# IO.net
KiCad netlist of a schematic drawn in Altium Designer
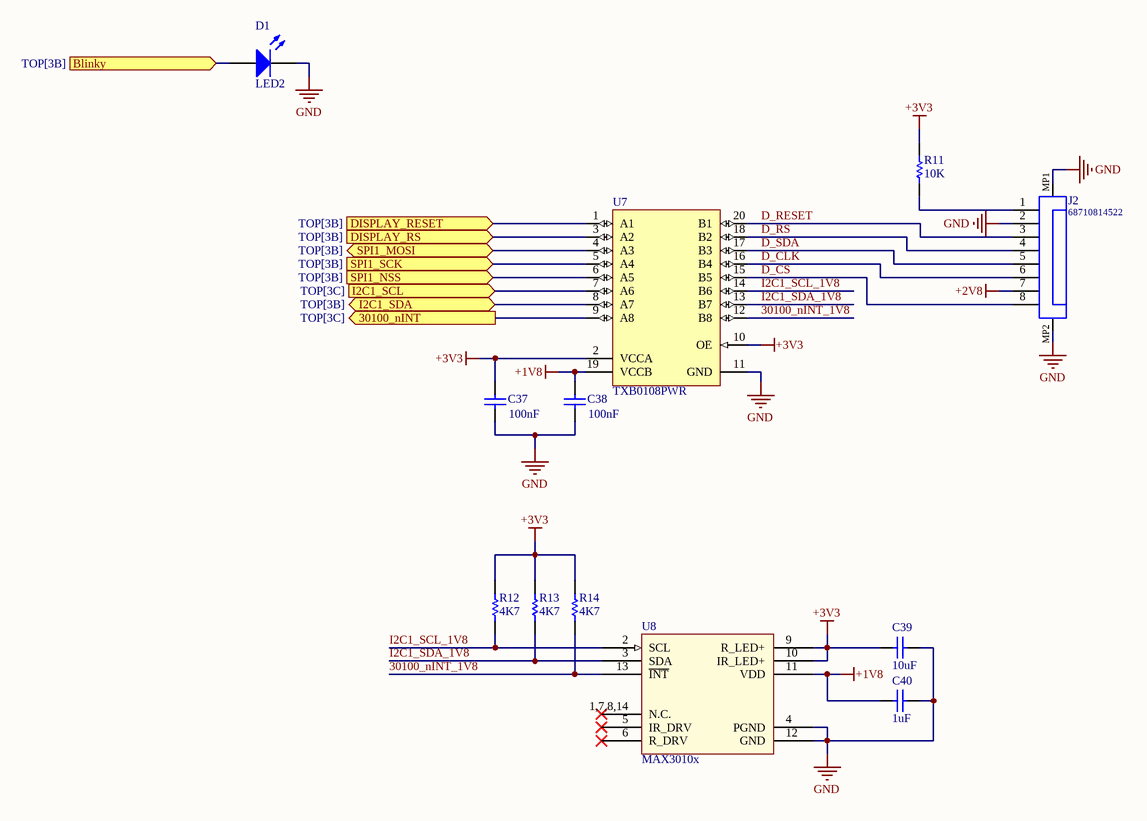
[diagram p0: IO.SchDoc]

(export (version "E")
  (design (tool "Eeschema 10.0.6"))
  (components
    (comp (ref "C37")
      (value "100nF")
      (footprint "C_0603")
      (description "Capacitor")
      (fields (field (name "Comment") "Cap") (field (name "PUBLISHER") "Altium Limited"))
      (libsource (lib "Miscellaneous Devices") (part "Cap"))
    )
    (comp (ref "C38")
      (value "100nF")
      (footprint "C_0603")
      (description "Capacitor")
      (fields (field (name "Comment") "Cap") (field (name "PUBLISHER") "Altium Limited"))
      (libsource (lib "Miscellaneous Devices") (part "Cap"))
    )
    (comp (ref "C39")
      (value "10uF")
      (footprint "C_0603")
      (description "Capacitor")
      (fields (field (name "Comment") "Cap") (field (name "PUBLISHER") "Altium Limited"))
      (libsource (lib "Miscellaneous Devices") (part "Cap"))
    )
    (comp (ref "C40")
      (value "1uF")
      (footprint "C_0603")
      (description "Capacitor")
      (fields (field (name "Comment") "Cap") (field (name "PUBLISHER") "Altium Limited"))
      (libsource (lib "Miscellaneous Devices") (part "Cap"))
    )
    (comp (ref "D1")
      (value "LED2")
      (footprint "D-0603")
      (description "Typical RED, GREEN, YELLOW, AMBER GaAs LED")
      (fields (field (name "PUBLISHER") "Altium Limited"))
      (libsource (lib "Miscellaneous Devices") (part "LED2"))
    )
    (comp (ref "J2")
      (value "68710814522")
      (footprint "68710814522")
      (description "SMT ZIF Connectors WR-FPC, Horizontal, Bottom Contact, pitch 0.5 mm, 8 pins")
      (fields (field (name "MANUFACTURER") "Wurth Elektronik") (field (name "PUBLISHER") "WurthElektronik"))
      (libsource (lib "Altium Content Vault") (part "WE-68X1081XXX22-8"))
    )
    (comp (ref "R11")
      (value "10K")
      (footprint "C_0603")
      (description "Resistor")
      (fields (field (name "Comment") "Res1") (field (name "PUBLISHER") "Altium Limited"))
      (libsource (lib "Miscellaneous Devices") (part "Res1"))
    )
    (comp (ref "R12")
      (value "4K7")
      (footprint "C_0603")
      (description "Resistor")
      (fields (field (name "Comment") "Res1") (field (name "PUBLISHER") "Altium Limited"))
      (libsource (lib "Miscellaneous Devices") (part "Res1"))
    )
    (comp (ref "R13")
      (value "4K7")
      (footprint "C_0603")
      (description "Resistor")
      (fields (field (name "Comment") "Res1") (field (name "PUBLISHER") "Altium Limited"))
      (libsource (lib "Miscellaneous Devices") (part "Res1"))
    )
    (comp (ref "R14")
      (value "4K7")
      (footprint "C_0603")
      (description "Resistor")
      (fields (field (name "Comment") "Res1") (field (name "PUBLISHER") "Altium Limited"))
      (libsource (lib "Miscellaneous Devices") (part "Res1"))
    )
    (comp (ref "U7")
      (value "TXB0108PWR")
      (footprint "PW0020A_L")
      (fields (field (name "MANUFACTURER") "Texas Instruments"))
      (libsource (lib "Altium Content Vault") (part "TI-TXB0108-PW-20"))
    )
    (comp (ref "U8")
      (value "MAX3010x")
      (footprint "OESIP14R560x330")
      (description "Pulse Oximeter and Heart-Rate Sensor IC  for Wearable Health")
      (libsource (lib "Max") (part "MAX3010x"))
    )
  )
  (nets
    (net (code "1") (name "+1V8") (class "Default")
      (node (ref "C38") (pin "2") (pinfunction "2_2") (pintype "passive"))
      (node (ref "C40") (pin "2") (pinfunction "2_2") (pintype "passive"))
      (node (ref "U7") (pin "19") (pinfunction "VCCB_19") (pintype "power_in"))
      (node (ref "U8") (pin "11") (pinfunction "VDD_11") (pintype "power_in"))
    )
    (net (code "2") (name "+2V8") (class "Default")
      (node (ref "J2") (pin "7") (pinfunction "7_7") (pintype "passive"))
    )
    (net (code "3") (name "+3V3") (class "Default")
      (node (ref "C37") (pin "2") (pinfunction "2_2") (pintype "passive"))
      (node (ref "C39") (pin "2") (pinfunction "2_2") (pintype "passive"))
      (node (ref "R11") (pin "1") (pinfunction "1_1") (pintype "passive"))
      (node (ref "R12") (pin "2") (pinfunction "2_2") (pintype "passive"))
      (node (ref "R13") (pin "2") (pinfunction "2_2") (pintype "passive"))
      (node (ref "R14") (pin "2") (pinfunction "2_2") (pintype "passive"))
      (node (ref "U7") (pin "10") (pinfunction "OE_10") (pintype "input"))
      (node (ref "U7") (pin "2") (pinfunction "VCCA_2") (pintype "power_in"))
      (node (ref "U8") (pin "10") (pinfunction "IR_LED+_10") (pintype "power_in"))
      (node (ref "U8") (pin "9") (pinfunction "R_LED+_9") (pintype "power_in"))
    )
    (net (code "4") (name "/30100_nINT") (class "Default")
      (node (ref "U7") (pin "9") (pinfunction "A8_9") (pintype "bidirectional"))
    )
    (net (code "5") (name "/30100_nINT_1V8") (class "Default")
      (node (ref "R14") (pin "1") (pinfunction "1_1") (pintype "passive"))
      (node (ref "U7") (pin "12") (pinfunction "B8_12") (pintype "bidirectional"))
      (node (ref "U8") (pin "13") (pinfunction "~{INT}_13") (pintype "open_collector"))
    )
    (net (code "6") (name "/Blinky") (class "Default")
      (node (ref "D1") (pin "1") (pinfunction "A_1") (pintype "passive"))
    )
    (net (code "7") (name "/DISPLAY_RESET") (class "Default")
      (node (ref "U7") (pin "1") (pinfunction "A1_1") (pintype "bidirectional"))
    )
    (net (code "8") (name "/DISPLAY_RS") (class "Default")
      (node (ref "U7") (pin "3") (pinfunction "A2_3") (pintype "bidirectional"))
    )
    (net (code "9") (name "/D_CLK") (class "Default")
      (node (ref "J2") (pin "6") (pinfunction "6_6") (pintype "passive"))
      (node (ref "U7") (pin "16") (pinfunction "B4_16") (pintype "bidirectional"))
    )
    (net (code "10") (name "/D_CS") (class "Default")
      (node (ref "J2") (pin "8") (pinfunction "8_8") (pintype "passive"))
      (node (ref "U7") (pin "15") (pinfunction "B5_15") (pintype "bidirectional"))
    )
    (net (code "11") (name "/D_RESET") (class "Default")
      (node (ref "J2") (pin "3") (pinfunction "3_3") (pintype "passive"))
      (node (ref "U7") (pin "20") (pinfunction "B1_20") (pintype "bidirectional"))
    )
    (net (code "12") (name "/D_RS") (class "Default")
      (node (ref "J2") (pin "4") (pinfunction "4_4") (pintype "passive"))
      (node (ref "U7") (pin "18") (pinfunction "B2_18") (pintype "bidirectional"))
    )
    (net (code "13") (name "/D_SDA") (class "Default")
      (node (ref "J2") (pin "5") (pinfunction "5_5") (pintype "passive"))
      (node (ref "U7") (pin "17") (pinfunction "B3_17") (pintype "bidirectional"))
    )
    (net (code "14") (name "/I2C1_SCL") (class "Default")
      (node (ref "U7") (pin "7") (pinfunction "A6_7") (pintype "bidirectional"))
    )
    (net (code "15") (name "/I2C1_SCL_1V8") (class "Default")
      (node (ref "R12") (pin "1") (pinfunction "1_1") (pintype "passive"))
      (node (ref "U7") (pin "14") (pinfunction "B6_14") (pintype "bidirectional"))
      (node (ref "U8") (pin "2") (pinfunction "SCL_2") (pintype "input"))
    )
    (net (code "16") (name "/I2C1_SDA") (class "Default")
      (node (ref "U7") (pin "8") (pinfunction "A7_8") (pintype "bidirectional"))
    )
    (net (code "17") (name "/I2C1_SDA_1V8") (class "Default")
      (node (ref "R13") (pin "1") (pinfunction "1_1") (pintype "passive"))
      (node (ref "U7") (pin "13") (pinfunction "B7_13") (pintype "bidirectional"))
      (node (ref "U8") (pin "3") (pinfunction "SDA_3") (pintype "open_collector"))
    )
    (net (code "18") (name "/SPI1_MOSI") (class "Default")
      (node (ref "U7") (pin "4") (pinfunction "A3_4") (pintype "bidirectional"))
    )
    (net (code "19") (name "/SPI1_NSS") (class "Default")
      (node (ref "U7") (pin "6") (pinfunction "A5_6") (pintype "bidirectional"))
    )
    (net (code "20") (name "/SPI1_SCK") (class "Default")
      (node (ref "U7") (pin "5") (pinfunction "A4_5") (pintype "bidirectional"))
    )
    (net (code "21") (name "GND") (class "Default")
      (node (ref "C37") (pin "1") (pinfunction "1_1") (pintype "passive"))
      (node (ref "C38") (pin "1") (pinfunction "1_1") (pintype "passive"))
      (node (ref "C39") (pin "1") (pinfunction "1_1") (pintype "passive"))
      (node (ref "C40") (pin "1") (pinfunction "1_1") (pintype "passive"))
      (node (ref "D1") (pin "2") (pinfunction "K_2") (pintype "passive"))
      (node (ref "J2") (pin "2") (pinfunction "2_2") (pintype "passive"))
      (node (ref "J2") (pin "MP1") (pinfunction "MP1_MP1") (pintype "passive"))
      (node (ref "J2") (pin "MP2") (pinfunction "MP2_MP2") (pintype "passive"))
      (node (ref "U7") (pin "11") (pinfunction "GND_11") (pintype "power_in"))
      (node (ref "U8") (pin "12") (pinfunction "GND_12") (pintype "power_in"))
      (node (ref "U8") (pin "4") (pinfunction "PGND_4") (pintype "power_in"))
    )
    (net (code "22") (name "Net-(J2-Pad1)") (class "Default")
      (node (ref "J2") (pin "1") (pinfunction "1_1") (pintype "passive"))
      (node (ref "R11") (pin "2") (pinfunction "2_2") (pintype "passive"))
    )
    (net (code "23") (name "unconnected-(U8-IR_DRV-Pad5)") (class "Default")
      (node (ref "U8") (pin "5") (pinfunction "IR_DRV_5") (pintype "passive+no_connect"))
    )
    (net (code "24") (name "unconnected-(U8-N.C.-Pad1)") (class "Default")
      (node (ref "U8") (pin "1") (pinfunction "N.C._1") (pintype "passive+no_connect"))
      (node (ref "U8") (pin "7") (pinfunction "N.C._7") (pintype "passive+no_connect"))
      (node (ref "U8") (pin "8") (pinfunction "N.C._8") (pintype "passive+no_connect"))
      (node (ref "U8") (pin "14") (pinfunction "N.C._14") (pintype "passive+no_connect"))
    )
    (net (code "25") (name "unconnected-(U8-R_DRV-Pad6)") (class "Default")
      (node (ref "U8") (pin "6") (pinfunction "R_DRV_6") (pintype "passive+no_connect"))
    )
  )
)
